# IGBT_half_bridge.net
KiCad netlist of a schematic drawn in Altium Designer
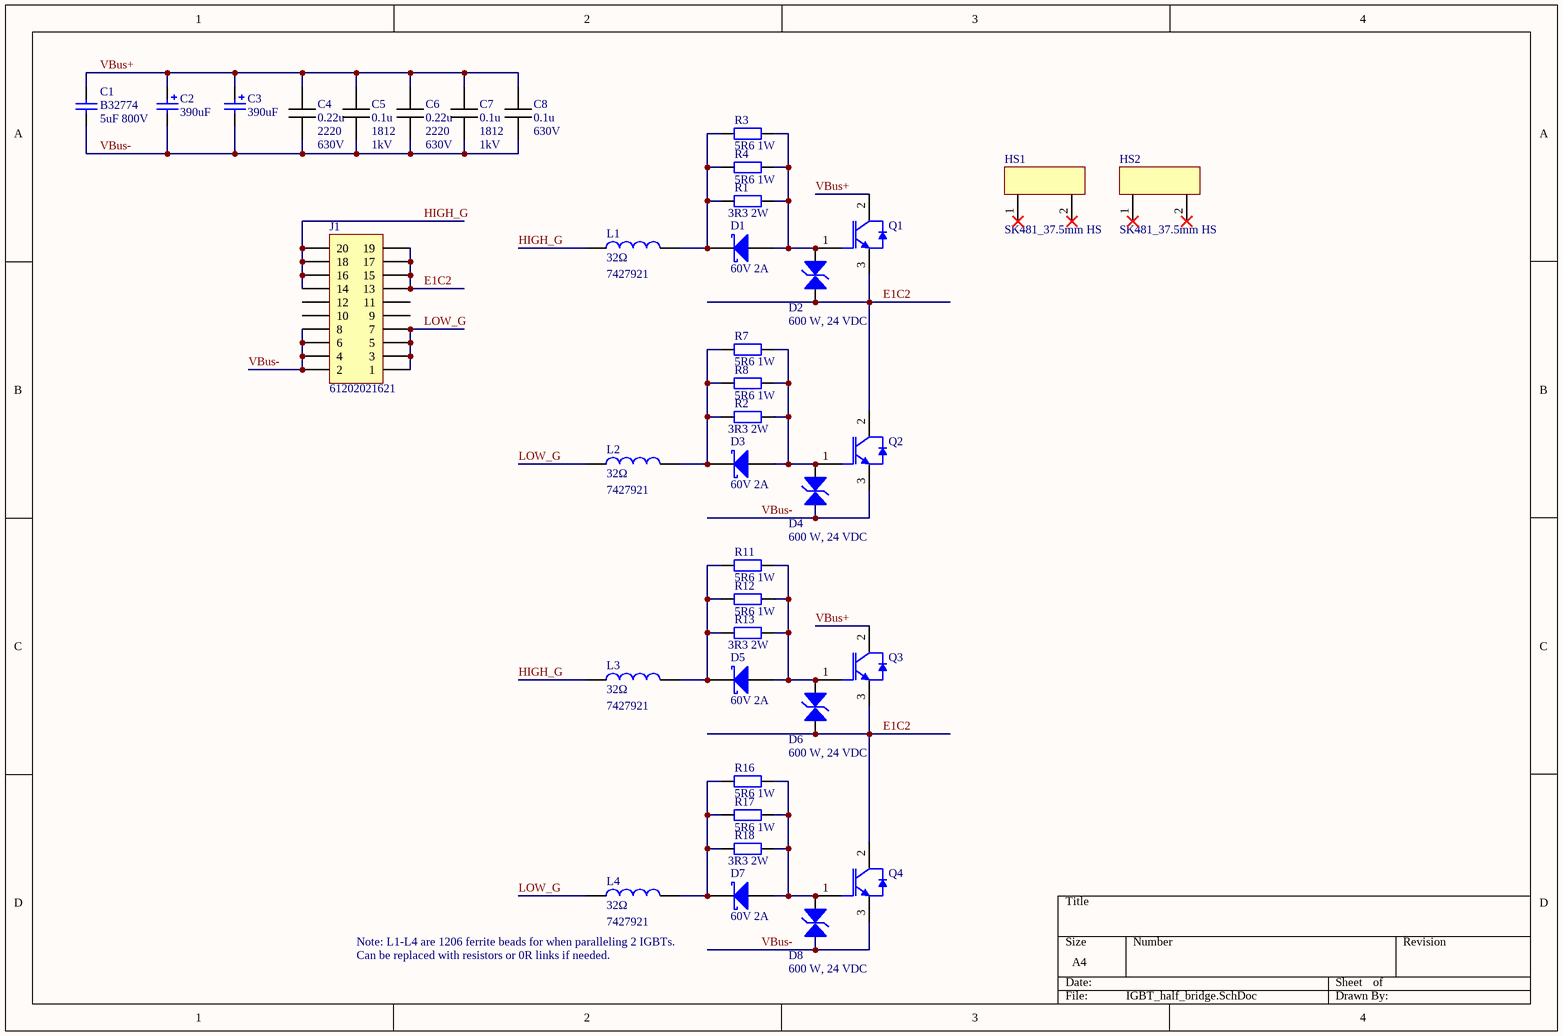
[diagram p0: IGBT_half_bridge.SchDoc]

(export (version "E")
  (design (tool "Eeschema 10.0.6"))
  (components
    (comp (ref "C1")
      (value "B32774")
      (footprint "B32774 5uF 800V")
      (description "Capacitor")
      (fields (field (name "ALTIUM_VALUE") "5uF 800V") (field (name "PUBLISHER") "Altium Limited"))
      (libsource (lib "Miscellaneous Devices") (part "Cap"))
    )
    (comp (ref "C2")
      (value "390uF")
      (footprint "WCAP-AIG8_30x46")
      (description "WCAP-AIG8 Aluminum Electrolytic Capacitors, 390uF")
      (fields (field (name "PARTNUMBER") "861011485019") (field (name "PUBLISHER") "Wurth Elektronik"))
      (libsource (lib "TV_Altium_library") (part "WCAP-AIG8, 861011485019"))
    )
    (comp (ref "C3")
      (value "390uF")
      (footprint "WCAP-AIG8_30x46")
      (description "WCAP-AIG8 Aluminum Electrolytic Capacitors, 390uF")
      (fields (field (name "PARTNUMBER") "861011485019") (field (name "PUBLISHER") "Wurth Elektronik"))
      (libsource (lib "TV_Altium_library") (part "WCAP-AIG8, 861011485019"))
    )
    (comp (ref "C4")
      (value "Capacitor")
      (footprint "2220C")
      (fields
        (field (name "CAPACITANCE") "0.22u")
        (field (name "PACKAGE") "2220")
        (field (name "VOLTAGE") "630V")
      )
      (libsource (lib "TV_Altium_library") (part "Capacitor"))
    )
    (comp (ref "C5")
      (value "Capacitor")
      (footprint "1812C")
      (fields
        (field (name "CAPACITANCE") "0.1u")
        (field (name "PACKAGE") "1812")
        (field (name "VOLTAGE") "1kV")
      )
      (libsource (lib "TV_Altium_library") (part "Capacitor"))
    )
    (comp (ref "C6")
      (value "Capacitor")
      (footprint "2220C")
      (fields
        (field (name "CAPACITANCE") "0.22u")
        (field (name "PACKAGE") "2220")
        (field (name "VOLTAGE") "630V")
      )
      (libsource (lib "TV_Altium_library") (part "Capacitor"))
    )
    (comp (ref "C7")
      (value "Capacitor")
      (footprint "1812C")
      (fields
        (field (name "CAPACITANCE") "0.1u")
        (field (name "PACKAGE") "1812")
        (field (name "VOLTAGE") "1kV")
      )
      (libsource (lib "TV_Altium_library") (part "Capacitor"))
    )
    (comp (ref "C8")
      (value "Capacitor")
      (footprint "Cap_multi_footprint")
      (fields (field (name "CAPACITANCE") "0.1u") (field (name "VOLTAGE") "630V"))
      (libsource (lib "TV_Altium_library") (part "Capacitor"))
    )
    (comp (ref "D1")
      (value "60V 2A")
      (footprint "DO-214AA_(SMB-J-BEND)_UNI")
      (description "SS26 Schottky rectifier")
      (libsource (lib "QCW Bridge PCBA") (part "SS26"))
    )
    (comp (ref "D2")
      (value "600 W, 24 VDC")
      (footprint "DO-214AA_Bidirectional")
      (description "WE-TVSP Power TVS Diode, bidirectional, 600 W, 24 VDC")
      (fields
        (field (name "PARTNO") "824521241")
        (field (name "MANUFACTURER") "Wurth Elektronik")
        (field (name "CREATED BY") "Baojun Chen")
      )
      (libsource (lib "QCW Bridge PCBA") (part "WE-TVSP DO-214AA, 824521241"))
    )
    (comp (ref "D3")
      (value "60V 2A")
      (footprint "DO-214AA_(SMB-J-BEND)_UNI")
      (description "SS26 Schottky rectifier")
      (libsource (lib "QCW Bridge PCBA") (part "SS26"))
    )
    (comp (ref "D4")
      (value "600 W, 24 VDC")
      (footprint "DO-214AA_Bidirectional")
      (description "WE-TVSP Power TVS Diode, bidirectional, 600 W, 24 VDC")
      (fields
        (field (name "PARTNO") "824521241")
        (field (name "MANUFACTURER") "Wurth Elektronik")
        (field (name "CREATED BY") "Baojun Chen")
      )
      (libsource (lib "QCW Bridge PCBA") (part "WE-TVSP DO-214AA, 824521241"))
    )
    (comp (ref "D5")
      (value "60V 2A")
      (footprint "DO-214AA_(SMB-J-BEND)_UNI")
      (description "SS26 Schottky rectifier")
      (libsource (lib "QCW Bridge PCBA") (part "SS26"))
    )
    (comp (ref "D6")
      (value "600 W, 24 VDC")
      (footprint "DO-214AA_Bidirectional")
      (description "WE-TVSP Power TVS Diode, bidirectional, 600 W, 24 VDC")
      (fields
        (field (name "PARTNO") "824521241")
        (field (name "MANUFACTURER") "Wurth Elektronik")
        (field (name "CREATED BY") "Baojun Chen")
      )
      (libsource (lib "QCW Bridge PCBA") (part "WE-TVSP DO-214AA, 824521241"))
    )
    (comp (ref "D7")
      (value "60V 2A")
      (footprint "DO-214AA_(SMB-J-BEND)_UNI")
      (description "SS26 Schottky rectifier")
      (libsource (lib "QCW Bridge PCBA") (part "SS26"))
    )
    (comp (ref "D8")
      (value "600 W, 24 VDC")
      (footprint "DO-214AA_Bidirectional")
      (description "WE-TVSP Power TVS Diode, bidirectional, 600 W, 24 VDC")
      (fields
        (field (name "PARTNO") "824521241")
        (field (name "MANUFACTURER") "Wurth Elektronik")
        (field (name "CREATED BY") "Baojun Chen")
      )
      (libsource (lib "QCW Bridge PCBA") (part "WE-TVSP DO-214AA, 824521241"))
    )
    (comp (ref "HS1")
      (value "SK481_37.5mm HS")
      (footprint "SK 481 37.5")
      (libsource (lib "QCW Bridge PCBA") (part "SK_481_37.5"))
    )
    (comp (ref "HS2")
      (value "SK481_37.5mm HS")
      (footprint "SK 481 37.5_FLIP")
      (libsource (lib "QCW Bridge PCBA") (part "SK_481_37.5"))
    )
    (comp (ref "J1")
      (value "61202021621")
      (footprint "61202021621")
      (description "WR-BHD 2.54mm Male Box Header")
      (fields (field (name "MANUFACTURER") "Wurth Elektronik") (field (name "CREATED BY") "Baojun Chen"))
      (libsource (lib "QCW Bridge PCBA") (part "61202021621"))
    )
    (comp (ref "L1")
      (value "32Ω")
      (footprint "WE-CBF_1206_High Speed")
      (description "WE-CBF SMD EMI Suppression Ferrite Bead, 1206, 32Ω")
      (fields (field (name "PARTNUMBER") "7427921") (field (name "PUBLISHER") "Wurth Elektronik"))
      (libsource (lib "QCW Bridge PCBA") (part "WE-CBF, 7427921"))
    )
    (comp (ref "L2")
      (value "32Ω")
      (footprint "WE-CBF_1206_High Speed")
      (description "WE-CBF SMD EMI Suppression Ferrite Bead, 1206, 32Ω")
      (fields (field (name "PARTNUMBER") "7427921") (field (name "PUBLISHER") "Wurth Elektronik"))
      (libsource (lib "QCW Bridge PCBA") (part "WE-CBF, 7427921"))
    )
    (comp (ref "L3")
      (value "32Ω")
      (footprint "WE-CBF_1206_High Speed")
      (description "WE-CBF SMD EMI Suppression Ferrite Bead, 1206, 32Ω")
      (fields (field (name "PARTNUMBER") "7427921") (field (name "PUBLISHER") "Wurth Elektronik"))
      (libsource (lib "QCW Bridge PCBA") (part "WE-CBF, 7427921"))
    )
    (comp (ref "L4")
      (value "32Ω")
      (footprint "WE-CBF_1206_High Speed")
      (description "WE-CBF SMD EMI Suppression Ferrite Bead, 1206, 32Ω")
      (fields (field (name "PARTNUMBER") "7427921") (field (name "PUBLISHER") "Wurth Elektronik"))
      (libsource (lib "QCW Bridge PCBA") (part "WE-CBF, 7427921"))
    )
    (comp (ref "Q1")
      (value "~")
      (footprint "TO-247")
      (description "IGBT, TO-247, Vertical")
      (libsource (lib "QCW Bridge PCBA") (part "TO-247_IGBT_V"))
    )
    (comp (ref "Q2")
      (value "~")
      (footprint "TO-247")
      (description "IGBT, TO-247, Vertical")
      (libsource (lib "QCW Bridge PCBA") (part "TO-247_IGBT_V"))
    )
    (comp (ref "Q3")
      (value "~")
      (footprint "TO-247")
      (description "IGBT, TO-247, Vertical")
      (libsource (lib "QCW Bridge PCBA") (part "TO-247_IGBT_V"))
    )
    (comp (ref "Q4")
      (value "~")
      (footprint "TO-247")
      (description "IGBT, TO-247, Vertical")
      (libsource (lib "QCW Bridge PCBA") (part "TO-247_IGBT_V"))
    )
    (comp (ref "R1")
      (value "3R3 2W")
      (footprint "Res_Radial_2W")
      (description "Resistor")
      (fields (field (name "PUBLISHER") "Altium Limited"))
      (libsource (lib "Miscellaneous Devices") (part "Res2"))
    )
    (comp (ref "R2")
      (value "3R3 2W")
      (footprint "Res_Radial_2W")
      (description "Resistor")
      (fields (field (name "PUBLISHER") "Altium Limited"))
      (libsource (lib "Miscellaneous Devices") (part "Res2"))
    )
    (comp (ref "R3")
      (value "5R6 1W")
      (description "Resistor")
      (fields (field (name "Comment") "Res2") (field (name "PUBLISHER") "Altium Limited"))
      (libsource (lib "Miscellaneous Devices") (part "Res2"))
    )
    (comp (ref "R4")
      (value "5R6 1W")
      (description "Resistor")
      (fields (field (name "Comment") "Res2") (field (name "PUBLISHER") "Altium Limited"))
      (libsource (lib "Miscellaneous Devices") (part "Res2"))
    )
    (comp (ref "R7")
      (value "5R6 1W")
      (description "Resistor")
      (fields (field (name "Comment") "Res2") (field (name "PUBLISHER") "Altium Limited"))
      (libsource (lib "Miscellaneous Devices") (part "Res2"))
    )
    (comp (ref "R8")
      (value "5R6 1W")
      (description "Resistor")
      (fields (field (name "Comment") "Res2") (field (name "PUBLISHER") "Altium Limited"))
      (libsource (lib "Miscellaneous Devices") (part "Res2"))
    )
    (comp (ref "R11")
      (value "5R6 1W")
      (description "Resistor")
      (fields (field (name "Comment") "Res2") (field (name "PUBLISHER") "Altium Limited"))
      (libsource (lib "Miscellaneous Devices") (part "Res2"))
    )
    (comp (ref "R12")
      (value "5R6 1W")
      (description "Resistor")
      (fields (field (name "Comment") "Res2") (field (name "PUBLISHER") "Altium Limited"))
      (libsource (lib "Miscellaneous Devices") (part "Res2"))
    )
    (comp (ref "R13")
      (value "3R3 2W")
      (footprint "Res_Radial_2W")
      (description "Resistor")
      (fields (field (name "PUBLISHER") "Altium Limited"))
      (libsource (lib "Miscellaneous Devices") (part "Res2"))
    )
    (comp (ref "R16")
      (value "5R6 1W")
      (description "Resistor")
      (fields (field (name "Comment") "Res2") (field (name "PUBLISHER") "Altium Limited"))
      (libsource (lib "Miscellaneous Devices") (part "Res2"))
    )
    (comp (ref "R17")
      (value "5R6 1W")
      (description "Resistor")
      (fields (field (name "Comment") "Res2") (field (name "PUBLISHER") "Altium Limited"))
      (libsource (lib "Miscellaneous Devices") (part "Res2"))
    )
    (comp (ref "R18")
      (value "3R3 2W")
      (footprint "Res_Radial_2W")
      (description "Resistor")
      (fields (field (name "PUBLISHER") "Altium Limited"))
      (libsource (lib "Miscellaneous Devices") (part "Res2"))
    )
  )
  (nets
    (net (code "1") (name "/E1C2") (class "Default")
      (node (ref "D2") (pin "2") (pinfunction "2_2") (pintype "passive"))
      (node (ref "D6") (pin "2") (pinfunction "2_2") (pintype "passive"))
      (node (ref "J1") (pin "13") (pinfunction "13_13") (pintype "passive"))
      (node (ref "J1") (pin "15") (pinfunction "15_15") (pintype "passive"))
      (node (ref "J1") (pin "17") (pinfunction "17_17") (pintype "passive"))
      (node (ref "J1") (pin "19") (pinfunction "19_19") (pintype "passive"))
      (node (ref "Q1") (pin "3") (pinfunction "E_3") (pintype "passive"))
      (node (ref "Q2") (pin "2") (pinfunction "C_2") (pintype "passive"))
      (node (ref "Q3") (pin "3") (pinfunction "E_3") (pintype "passive"))
      (node (ref "Q4") (pin "2") (pinfunction "C_2") (pintype "passive"))
    )
    (net (code "2") (name "/HIGH_G") (class "Default")
      (node (ref "J1") (pin "14") (pinfunction "14_14") (pintype "passive"))
      (node (ref "J1") (pin "16") (pinfunction "16_16") (pintype "passive"))
      (node (ref "J1") (pin "18") (pinfunction "18_18") (pintype "passive"))
      (node (ref "J1") (pin "20") (pinfunction "20_20") (pintype "passive"))
      (node (ref "L1") (pin "1") (pinfunction "1_1") (pintype "passive"))
      (node (ref "L3") (pin "1") (pinfunction "1_1") (pintype "passive"))
    )
    (net (code "3") (name "/LOW_G") (class "Default")
      (node (ref "J1") (pin "1") (pinfunction "1_1") (pintype "passive"))
      (node (ref "J1") (pin "3") (pinfunction "3_3") (pintype "passive"))
      (node (ref "J1") (pin "5") (pinfunction "5_5") (pintype "passive"))
      (node (ref "J1") (pin "7") (pinfunction "7_7") (pintype "passive"))
      (node (ref "L2") (pin "1") (pinfunction "1_1") (pintype "passive"))
      (node (ref "L4") (pin "1") (pinfunction "1_1") (pintype "passive"))
    )
    (net (code "4") (name "/VBus+") (class "Default")
      (node (ref "C1") (pin "1") (pinfunction "1_1") (pintype "passive"))
      (node (ref "C2") (pin "1") (pinfunction "1_1") (pintype "passive"))
      (node (ref "C3") (pin "1") (pinfunction "1_1") (pintype "passive"))
      (node (ref "C4") (pin "1") (pinfunction "1_1") (pintype "passive"))
      (node (ref "C5") (pin "1") (pinfunction "1_1") (pintype "passive"))
      (node (ref "C6") (pin "1") (pinfunction "1_1") (pintype "passive"))
      (node (ref "C7") (pin "1") (pinfunction "1_1") (pintype "passive"))
      (node (ref "C8") (pin "2") (pinfunction "2_2") (pintype "passive"))
      (node (ref "Q1") (pin "2") (pinfunction "C_2") (pintype "passive"))
      (node (ref "Q3") (pin "2") (pinfunction "C_2") (pintype "passive"))
    )
    (net (code "5") (name "/VBus-") (class "Default")
      (node (ref "C1") (pin "2") (pinfunction "2_2") (pintype "passive"))
      (node (ref "C2") (pin "2") (pinfunction "2_2") (pintype "passive"))
      (node (ref "C3") (pin "2") (pinfunction "2_2") (pintype "passive"))
      (node (ref "C4") (pin "2") (pinfunction "2_2") (pintype "passive"))
      (node (ref "C5") (pin "2") (pinfunction "2_2") (pintype "passive"))
      (node (ref "C6") (pin "2") (pinfunction "2_2") (pintype "passive"))
      (node (ref "C7") (pin "2") (pinfunction "2_2") (pintype "passive"))
      (node (ref "C8") (pin "1") (pinfunction "1_1") (pintype "passive"))
      (node (ref "D4") (pin "2") (pinfunction "2_2") (pintype "passive"))
      (node (ref "D8") (pin "2") (pinfunction "2_2") (pintype "passive"))
      (node (ref "J1") (pin "2") (pinfunction "2_2") (pintype "passive"))
      (node (ref "J1") (pin "4") (pinfunction "4_4") (pintype "passive"))
      (node (ref "J1") (pin "6") (pinfunction "6_6") (pintype "passive"))
      (node (ref "J1") (pin "8") (pinfunction "8_8") (pintype "passive"))
      (node (ref "Q2") (pin "3") (pinfunction "E_3") (pintype "passive"))
      (node (ref "Q4") (pin "3") (pinfunction "E_3") (pintype "passive"))
    )
    (net (code "6") (name "Net-(D1-PadK)") (class "Default")
      (node (ref "D1") (pin "K") (pinfunction "K_K") (pintype "passive"))
      (node (ref "L1") (pin "2") (pinfunction "2_2") (pintype "passive"))
      (node (ref "R1") (pin "1") (pinfunction "1_1") (pintype "passive"))
      (node (ref "R3") (pin "1") (pinfunction "1_1") (pintype "passive"))
      (node (ref "R4") (pin "1") (pinfunction "1_1") (pintype "passive"))
    )
    (net (code "7") (name "Net-(D3-PadK)") (class "Default")
      (node (ref "D3") (pin "K") (pinfunction "K_K") (pintype "passive"))
      (node (ref "L2") (pin "2") (pinfunction "2_2") (pintype "passive"))
      (node (ref "R2") (pin "1") (pinfunction "1_1") (pintype "passive"))
      (node (ref "R7") (pin "1") (pinfunction "1_1") (pintype "passive"))
      (node (ref "R8") (pin "1") (pinfunction "1_1") (pintype "passive"))
    )
    (net (code "8") (name "Net-(D5-PadK)") (class "Default")
      (node (ref "D5") (pin "K") (pinfunction "K_K") (pintype "passive"))
      (node (ref "L3") (pin "2") (pinfunction "2_2") (pintype "passive"))
      (node (ref "R11") (pin "1") (pinfunction "1_1") (pintype "passive"))
      (node (ref "R12") (pin "1") (pinfunction "1_1") (pintype "passive"))
      (node (ref "R13") (pin "1") (pinfunction "1_1") (pintype "passive"))
    )
    (net (code "9") (name "Net-(D7-PadK)") (class "Default")
      (node (ref "D7") (pin "K") (pinfunction "K_K") (pintype "passive"))
      (node (ref "L4") (pin "2") (pinfunction "2_2") (pintype "passive"))
      (node (ref "R16") (pin "1") (pinfunction "1_1") (pintype "passive"))
      (node (ref "R17") (pin "1") (pinfunction "1_1") (pintype "passive"))
      (node (ref "R18") (pin "1") (pinfunction "1_1") (pintype "passive"))
    )
    (net (code "10") (name "Net-(Q1-G)") (class "Default")
      (node (ref "D1") (pin "A") (pinfunction "A_A") (pintype "passive"))
      (node (ref "D2") (pin "1") (pinfunction "1_1") (pintype "passive"))
      (node (ref "Q1") (pin "1") (pinfunction "G_1") (pintype "passive"))
      (node (ref "R1") (pin "2") (pinfunction "2_2") (pintype "passive"))
      (node (ref "R3") (pin "2") (pinfunction "2_2") (pintype "passive"))
      (node (ref "R4") (pin "2") (pinfunction "2_2") (pintype "passive"))
    )
    (net (code "11") (name "Net-(Q2-G)") (class "Default")
      (node (ref "D3") (pin "A") (pinfunction "A_A") (pintype "passive"))
      (node (ref "D4") (pin "1") (pinfunction "1_1") (pintype "passive"))
      (node (ref "Q2") (pin "1") (pinfunction "G_1") (pintype "passive"))
      (node (ref "R2") (pin "2") (pinfunction "2_2") (pintype "passive"))
      (node (ref "R7") (pin "2") (pinfunction "2_2") (pintype "passive"))
      (node (ref "R8") (pin "2") (pinfunction "2_2") (pintype "passive"))
    )
    (net (code "12") (name "Net-(Q3-G)") (class "Default")
      (node (ref "D5") (pin "A") (pinfunction "A_A") (pintype "passive"))
      (node (ref "D6") (pin "1") (pinfunction "1_1") (pintype "passive"))
      (node (ref "Q3") (pin "1") (pinfunction "G_1") (pintype "passive"))
      (node (ref "R11") (pin "2") (pinfunction "2_2") (pintype "passive"))
      (node (ref "R12") (pin "2") (pinfunction "2_2") (pintype "passive"))
      (node (ref "R13") (pin "2") (pinfunction "2_2") (pintype "passive"))
    )
    (net (code "13") (name "Net-(Q4-G)") (class "Default")
      (node (ref "D7") (pin "A") (pinfunction "A_A") (pintype "passive"))
      (node (ref "D8") (pin "1") (pinfunction "1_1") (pintype "passive"))
      (node (ref "Q4") (pin "1") (pinfunction "G_1") (pintype "passive"))
      (node (ref "R16") (pin "2") (pinfunction "2_2") (pintype "passive"))
      (node (ref "R17") (pin "2") (pinfunction "2_2") (pintype "passive"))
      (node (ref "R18") (pin "2") (pinfunction "2_2") (pintype "passive"))
    )
    (net (code "14") (name "unconnected-(HS1-Pad1)") (class "Default")
      (node (ref "HS1") (pin "1") (pinfunction "1_1") (pintype "passive+no_connect"))
    )
    (net (code "15") (name "unconnected-(HS1-Pad2)") (class "Default")
      (node (ref "HS1") (pin "2") (pinfunction "2_2") (pintype "passive+no_connect"))
    )
    (net (code "16") (name "unconnected-(HS2-Pad1)") (class "Default")
      (node (ref "HS2") (pin "1") (pinfunction "1_1") (pintype "passive+no_connect"))
    )
    (net (code "17") (name "unconnected-(HS2-Pad2)") (class "Default")
      (node (ref "HS2") (pin "2") (pinfunction "2_2") (pintype "passive+no_connect"))
    )
    (net (code "18") (name "unconnected-(J1-Pad9)") (class "Default")
      (node (ref "J1") (pin "9") (pinfunction "9_9") (pintype "passive"))
    )
    (net (code "19") (name "unconnected-(J1-Pad10)") (class "Default")
      (node (ref "J1") (pin "10") (pinfunction "10_10") (pintype "passive"))
    )
    (net (code "20") (name "unconnected-(J1-Pad11)") (class "Default")
      (node (ref "J1") (pin "11") (pinfunction "11_11") (pintype "passive"))
    )
    (net (code "21") (name "unconnected-(J1-Pad12)") (class "Default")
      (node (ref "J1") (pin "12") (pinfunction "12_12") (pintype "passive"))
    )
  )
)
